# stm32f103c8t6.net
KiCad netlist of a schematic drawn in Altium Designer
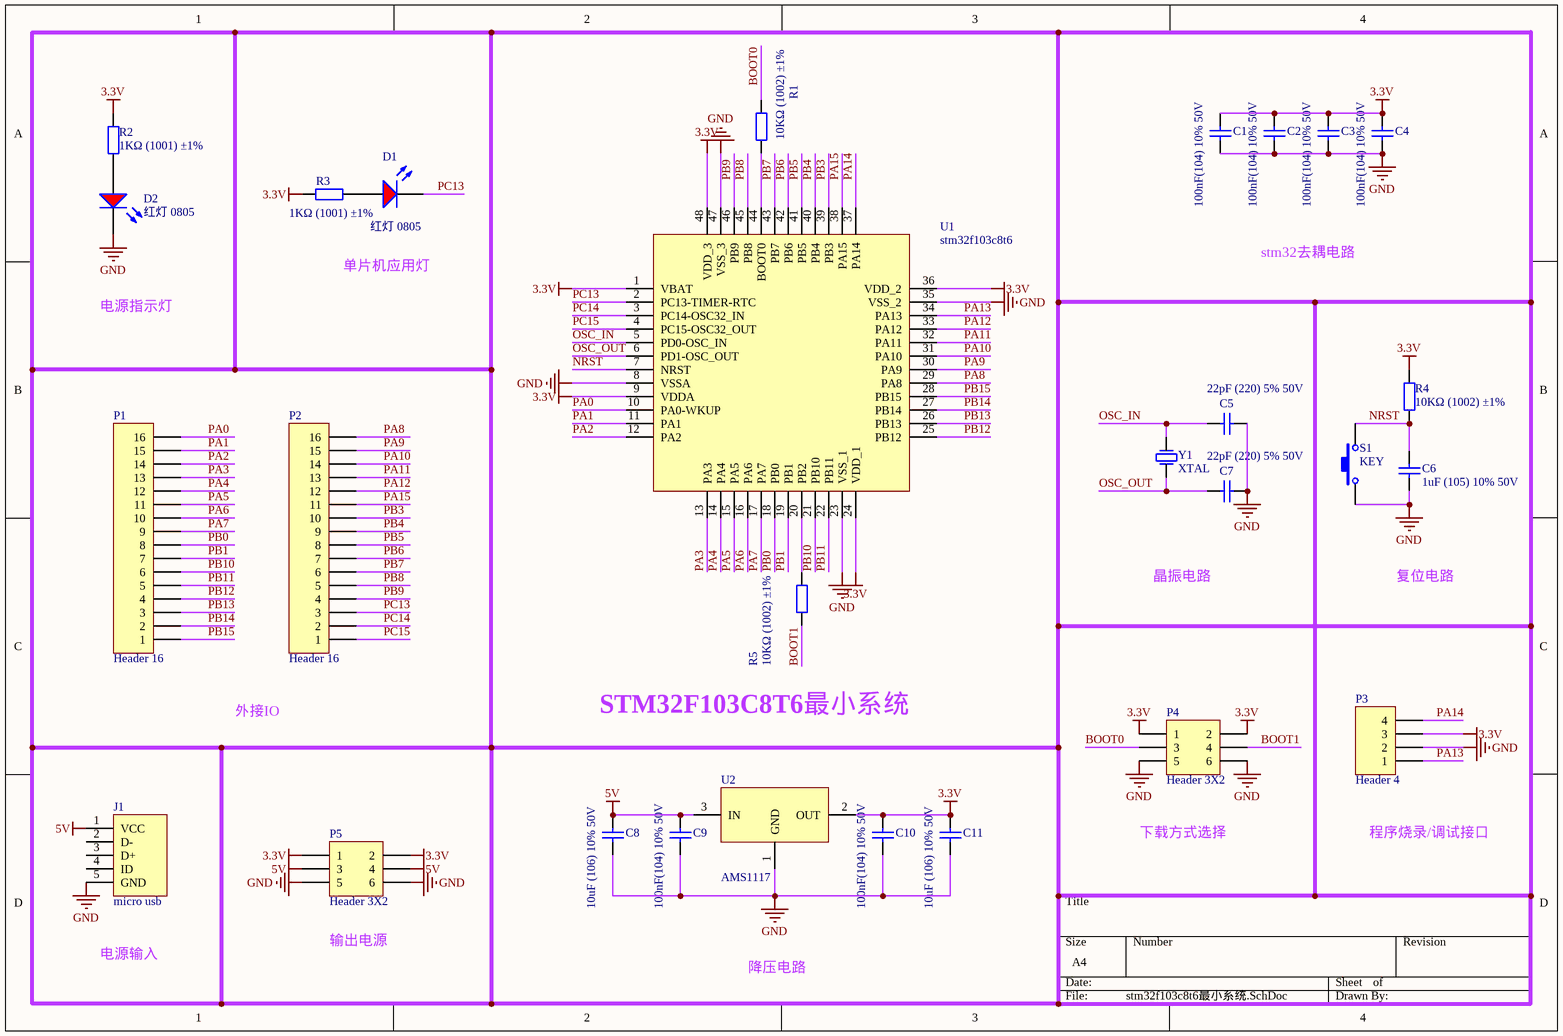
[diagram p0: stm32f103c8t6最小系统.SchDoc]

(export (version "E")
  (design (tool "Eeschema 10.0.6"))
  (components
    (comp (ref "C1")
      (value "100nF(104) 10% 50V")
      (footprint "0805_C")
      (description "贴片电容")
      (libsource (lib "Miscellaneous Devices LC") (part "0805 100nF(104) 10% 50V"))
    )
    (comp (ref "C2")
      (value "100nF(104) 10% 50V")
      (footprint "0805_C")
      (description "贴片电容")
      (libsource (lib "Miscellaneous Devices LC") (part "0805 100nF(104) 10% 50V"))
    )
    (comp (ref "C3")
      (value "100nF(104) 10% 50V")
      (footprint "0805_C")
      (description "贴片电容")
      (libsource (lib "Miscellaneous Devices LC") (part "0805 100nF(104) 10% 50V"))
    )
    (comp (ref "C4")
      (value "100nF(104) 10% 50V")
      (footprint "0805_C")
      (description "贴片电容")
      (libsource (lib "Miscellaneous Devices LC") (part "0805 100nF(104) 10% 50V"))
    )
    (comp (ref "C5")
      (value "22pF (220) 5% 50V")
      (footprint "0805_C")
      (description "贴片电容")
      (libsource (lib "Miscellaneous Devices LC") (part "0805 22pF (220) 5% 50V"))
    )
    (comp (ref "C6")
      (value "1uF (105) 10% 50V")
      (footprint "0805_C")
      (description "贴片电容")
      (libsource (lib "Miscellaneous Devices LC") (part "0805 1uF (105) 10% 50V"))
    )
    (comp (ref "C7")
      (value "22pF (220) 5% 50V")
      (footprint "0805_C")
      (description "贴片电容")
      (libsource (lib "Miscellaneous Devices LC") (part "0805 22pF (220) 5% 50V"))
    )
    (comp (ref "C8")
      (value "10uF (106) 10% 50V")
      (footprint "1206_C")
      (description "贴片电容")
      (libsource (lib "Miscellaneous Devices LC") (part "1206 10uF (106) 10% 50V"))
    )
    (comp (ref "C9")
      (value "100nF(104) 10% 50V")
      (footprint "0805_C")
      (description "贴片电容")
      (libsource (lib "Miscellaneous Devices LC") (part "0805 100nF(104) 10% 50V"))
    )
    (comp (ref "C10")
      (value "100nF(104) 10% 50V")
      (footprint "0805_C")
      (description "贴片电容")
      (libsource (lib "Miscellaneous Devices LC") (part "0805 100nF(104) 10% 50V"))
    )
    (comp (ref "C11")
      (value "10uF (106) 10% 50V")
      (footprint "1206_C")
      (description "贴片电容")
      (libsource (lib "Miscellaneous Devices LC") (part "1206 10uF (106) 10% 50V"))
    )
    (comp (ref "D1")
      (value "红灯 0805")
      (footprint "0805_LED_S1")
      (description "发光二极管")
      (libsource (lib "Miscellaneous Devices LC") (part "0805 红灯"))
    )
    (comp (ref "D2")
      (value "红灯 0805")
      (footprint "0805_LED_S1")
      (description "发光二极管")
      (libsource (lib "Miscellaneous Devices LC") (part "0805 红灯"))
    )
    (comp (ref "J1")
      (value "micro usb")
      (footprint "micro usb")
      (libsource (lib "stm32f103c8t6最小系统") (part "micro usb"))
    )
    (comp (ref "P1")
      (value "Header 16")
      (footprint "HDR1X16")
      (description "Header, 16-Pin")
      (fields (field (name "PUBLISHER") "Altium Limited"))
      (libsource (lib "base") (part "Header 16"))
    )
    (comp (ref "P2")
      (value "Header 16")
      (footprint "HDR1X16")
      (description "Header, 16-Pin")
      (fields (field (name "PUBLISHER") "Altium Limited"))
      (libsource (lib "base") (part "Header 16"))
    )
    (comp (ref "P3")
      (value "Header 4")
      (footprint "HDR1X4")
      (description "Header, 4-Pin")
      (fields (field (name "PUBLISHER") "Altium Limited"))
      (libsource (lib "base") (part "Header 4"))
    )
    (comp (ref "P4")
      (value "Header 3X2")
      (footprint "HDR2X3")
      (description "Header, 3-Pin, Dual row")
      (fields (field (name "PUBLISHER") "Altium Limited"))
      (libsource (lib "base") (part "Header 3X2"))
    )
    (comp (ref "P5")
      (value "Header 3X2")
      (footprint "HDR2X3")
      (description "Header, 3-Pin, Dual row")
      (fields (field (name "PUBLISHER") "Altium Limited"))
      (libsource (lib "base") (part "Header 3X2"))
    )
    (comp (ref "R1")
      (value "10KΩ (1002) ±1%")
      (footprint "0805_R")
      (description "贴片电阻")
      (libsource (lib "Miscellaneous Devices LC") (part "0805 10KΩ (1002) 1%"))
    )
    (comp (ref "R2")
      (value "1KΩ (1001) ±1%")
      (footprint "0805_R")
      (description "贴片电阻")
      (libsource (lib "") (part "0805 1KΩ (1001) 1%_1"))
    )
    (comp (ref "R3")
      (value "1KΩ (1001) ±1%")
      (footprint "0805_R")
      (description "贴片电阻")
      (libsource (lib "Miscellaneous Devices LC") (part "0805 1KΩ (1001) 1%"))
    )
    (comp (ref "R4")
      (value "10KΩ (1002) ±1%")
      (footprint "0805_R")
      (description "贴片电阻")
      (libsource (lib "Miscellaneous Devices LC") (part "0805 10KΩ (1002) 1%"))
    )
    (comp (ref "R5")
      (value "10KΩ (1002) ±1%")
      (footprint "0805_R")
      (description "贴片电阻")
      (libsource (lib "Miscellaneous Devices LC") (part "0805 10KΩ (1002) 1%"))
    )
    (comp (ref "S1") (value "KEY") (footprint "KEY") (libsource (lib "stm32f103c8t6最小系统") (part "KEY")))
    (comp (ref "U1")
      (value "stm32f103c8t6")
      (footprint "stm32f103c8t6")
      (libsource (lib "stm32f103c8t6最小系统") (part "stm32f103c8t6"))
    )
    (comp (ref "U2")
      (value "AMS1117")
      (footprint "AMS1117")
      (libsource (lib "stm32f103c8t6最小系统") (part "AMS1117"))
    )
    (comp (ref "Y1") (value "XTAL") (footprint "XTAL") (libsource (lib "stm32f103c8t6最小系统") (part "XTAL")))
  )
  (nets
    (net (code "1") (name "/BOOT0") (class "Default")
      (node (ref "P4") (pin "3") (pinfunction "3_3") (pintype "passive"))
      (node (ref "R1") (pin "2") (pinfunction "2_2") (pintype "passive"))
    )
    (net (code "2") (name "/BOOT1") (class "Default")
      (node (ref "P4") (pin "4") (pinfunction "4_4") (pintype "passive"))
      (node (ref "R5") (pin "1") (pinfunction "1_1") (pintype "passive"))
    )
    (net (code "3") (name "/NRST") (class "Default")
      (node (ref "C6") (pin "2") (pinfunction "2_2") (pintype "passive"))
      (node (ref "R4") (pin "1") (pinfunction "1_1") (pintype "passive"))
      (node (ref "S1") (pin "2") (pinfunction "2_2") (pintype "power_in"))
      (node (ref "U1") (pin "7") (pinfunction "NRST_7") (pintype "power_in"))
    )
    (net (code "4") (name "/OSC_IN") (class "Default")
      (node (ref "C5") (pin "1") (pinfunction "1_1") (pintype "passive"))
      (node (ref "U1") (pin "5") (pinfunction "PD0-OSC_IN_5") (pintype "power_in"))
      (node (ref "Y1") (pin "2") (pinfunction "2_2") (pintype "power_in"))
    )
    (net (code "5") (name "/OSC_OUT") (class "Default")
      (node (ref "C7") (pin "1") (pinfunction "1_1") (pintype "passive"))
      (node (ref "U1") (pin "6") (pinfunction "PD1-OSC_OUT_6") (pintype "power_in"))
      (node (ref "Y1") (pin "1") (pinfunction "1_1") (pintype "power_in"))
    )
    (net (code "6") (name "/PA0") (class "Default")
      (node (ref "P1") (pin "16") (pinfunction "16_16") (pintype "passive"))
      (node (ref "U1") (pin "10") (pinfunction "PA0-WKUP_10") (pintype "power_in"))
    )
    (net (code "7") (name "/PA1") (class "Default")
      (node (ref "P1") (pin "15") (pinfunction "15_15") (pintype "passive"))
      (node (ref "U1") (pin "11") (pinfunction "PA1_11") (pintype "power_in"))
    )
    (net (code "8") (name "/PA2") (class "Default")
      (node (ref "P1") (pin "14") (pinfunction "14_14") (pintype "passive"))
      (node (ref "U1") (pin "12") (pinfunction "PA2_12") (pintype "power_in"))
    )
    (net (code "9") (name "/PA3") (class "Default")
      (node (ref "P1") (pin "13") (pinfunction "13_13") (pintype "passive"))
      (node (ref "U1") (pin "13") (pinfunction "PA3_13") (pintype "power_in"))
    )
    (net (code "10") (name "/PA4") (class "Default")
      (node (ref "P1") (pin "12") (pinfunction "12_12") (pintype "passive"))
      (node (ref "U1") (pin "14") (pinfunction "PA4_14") (pintype "power_in"))
    )
    (net (code "11") (name "/PA5") (class "Default")
      (node (ref "P1") (pin "11") (pinfunction "11_11") (pintype "passive"))
      (node (ref "U1") (pin "15") (pinfunction "PA5_15") (pintype "power_in"))
    )
    (net (code "12") (name "/PA6") (class "Default")
      (node (ref "P1") (pin "10") (pinfunction "10_10") (pintype "passive"))
      (node (ref "U1") (pin "16") (pinfunction "PA6_16") (pintype "power_in"))
    )
    (net (code "13") (name "/PA7") (class "Default")
      (node (ref "P1") (pin "9") (pinfunction "9_9") (pintype "passive"))
      (node (ref "U1") (pin "17") (pinfunction "PA7_17") (pintype "power_in"))
    )
    (net (code "14") (name "/PA8") (class "Default")
      (node (ref "P2") (pin "16") (pinfunction "16_16") (pintype "passive"))
      (node (ref "U1") (pin "29") (pinfunction "PA8_29") (pintype "power_in"))
    )
    (net (code "15") (name "/PA9") (class "Default")
      (node (ref "P2") (pin "15") (pinfunction "15_15") (pintype "passive"))
      (node (ref "U1") (pin "30") (pinfunction "PA9_30") (pintype "power_in"))
    )
    (net (code "16") (name "/PA10") (class "Default")
      (node (ref "P2") (pin "14") (pinfunction "14_14") (pintype "passive"))
      (node (ref "U1") (pin "31") (pinfunction "PA10_31") (pintype "power_in"))
    )
    (net (code "17") (name "/PA11") (class "Default")
      (node (ref "P2") (pin "13") (pinfunction "13_13") (pintype "passive"))
      (node (ref "U1") (pin "32") (pinfunction "PA11_32") (pintype "power_in"))
    )
    (net (code "18") (name "/PA12") (class "Default")
      (node (ref "P2") (pin "12") (pinfunction "12_12") (pintype "passive"))
      (node (ref "U1") (pin "33") (pinfunction "PA12_33") (pintype "power_in"))
    )
    (net (code "19") (name "/PA13") (class "Default")
      (node (ref "P3") (pin "1") (pinfunction "1_1") (pintype "passive"))
      (node (ref "U1") (pin "34") (pinfunction "PA13_34") (pintype "power_in"))
    )
    (net (code "20") (name "/PA14") (class "Default")
      (node (ref "P3") (pin "4") (pinfunction "4_4") (pintype "passive"))
      (node (ref "U1") (pin "37") (pinfunction "PA14_37") (pintype "power_in"))
    )
    (net (code "21") (name "/PA15") (class "Default")
      (node (ref "P2") (pin "11") (pinfunction "11_11") (pintype "passive"))
      (node (ref "U1") (pin "38") (pinfunction "PA15_38") (pintype "power_in"))
    )
    (net (code "22") (name "/PB0") (class "Default")
      (node (ref "P1") (pin "8") (pinfunction "8_8") (pintype "passive"))
      (node (ref "U1") (pin "18") (pinfunction "PB0_18") (pintype "power_in"))
    )
    (net (code "23") (name "/PB1") (class "Default")
      (node (ref "P1") (pin "7") (pinfunction "7_7") (pintype "passive"))
      (node (ref "U1") (pin "19") (pinfunction "PB1_19") (pintype "power_in"))
    )
    (net (code "24") (name "/PB3") (class "Default")
      (node (ref "P2") (pin "10") (pinfunction "10_10") (pintype "passive"))
      (node (ref "U1") (pin "39") (pinfunction "PB3_39") (pintype "power_in"))
    )
    (net (code "25") (name "/PB4") (class "Default")
      (node (ref "P2") (pin "9") (pinfunction "9_9") (pintype "passive"))
      (node (ref "U1") (pin "40") (pinfunction "PB4_40") (pintype "power_in"))
    )
    (net (code "26") (name "/PB5") (class "Default")
      (node (ref "P2") (pin "8") (pinfunction "8_8") (pintype "passive"))
      (node (ref "U1") (pin "41") (pinfunction "PB5_41") (pintype "power_in"))
    )
    (net (code "27") (name "/PB6") (class "Default")
      (node (ref "P2") (pin "7") (pinfunction "7_7") (pintype "passive"))
      (node (ref "U1") (pin "42") (pinfunction "PB6_42") (pintype "power_in"))
    )
    (net (code "28") (name "/PB7") (class "Default")
      (node (ref "P2") (pin "6") (pinfunction "6_6") (pintype "passive"))
      (node (ref "U1") (pin "43") (pinfunction "PB7_43") (pintype "power_in"))
    )
    (net (code "29") (name "/PB8") (class "Default")
      (node (ref "P2") (pin "5") (pinfunction "5_5") (pintype "passive"))
      (node (ref "U1") (pin "45") (pinfunction "PB8_45") (pintype "power_in"))
    )
    (net (code "30") (name "/PB9") (class "Default")
      (node (ref "P2") (pin "4") (pinfunction "4_4") (pintype "passive"))
      (node (ref "U1") (pin "46") (pinfunction "PB9_46") (pintype "power_in"))
    )
    (net (code "31") (name "/PB10") (class "Default")
      (node (ref "P1") (pin "6") (pinfunction "6_6") (pintype "passive"))
      (node (ref "U1") (pin "21") (pinfunction "PB10_21") (pintype "power_in"))
    )
    (net (code "32") (name "/PB11") (class "Default")
      (node (ref "P1") (pin "5") (pinfunction "5_5") (pintype "passive"))
      (node (ref "U1") (pin "22") (pinfunction "PB11_22") (pintype "power_in"))
    )
    (net (code "33") (name "/PB12") (class "Default")
      (node (ref "P1") (pin "4") (pinfunction "4_4") (pintype "passive"))
      (node (ref "U1") (pin "25") (pinfunction "PB12_25") (pintype "power_in"))
    )
    (net (code "34") (name "/PB13") (class "Default")
      (node (ref "P1") (pin "3") (pinfunction "3_3") (pintype "passive"))
      (node (ref "U1") (pin "26") (pinfunction "PB13_26") (pintype "power_in"))
    )
    (net (code "35") (name "/PB14") (class "Default")
      (node (ref "P1") (pin "2") (pinfunction "2_2") (pintype "passive"))
      (node (ref "U1") (pin "27") (pinfunction "PB14_27") (pintype "power_in"))
    )
    (net (code "36") (name "/PB15") (class "Default")
      (node (ref "P1") (pin "1") (pinfunction "1_1") (pintype "passive"))
      (node (ref "U1") (pin "28") (pinfunction "PB15_28") (pintype "power_in"))
    )
    (net (code "37") (name "/PC13") (class "Default")
      (node (ref "D1") (pin "K") (pinfunction "K_K") (pintype "passive"))
      (node (ref "P2") (pin "3") (pinfunction "3_3") (pintype "passive"))
      (node (ref "U1") (pin "2") (pinfunction "PC13-TIMER-RTC_2") (pintype "power_in"))
    )
    (net (code "38") (name "/PC14") (class "Default")
      (node (ref "P2") (pin "2") (pinfunction "2_2") (pintype "passive"))
      (node (ref "U1") (pin "3") (pinfunction "PC14-OSC32_IN_3") (pintype "power_in"))
    )
    (net (code "39") (name "/PC15") (class "Default")
      (node (ref "P2") (pin "1") (pinfunction "1_1") (pintype "passive"))
      (node (ref "U1") (pin "4") (pinfunction "PC15-OSC32_OUT_4") (pintype "power_in"))
    )
    (net (code "40") (name "3.3V") (class "Default")
      (node (ref "C1") (pin "2") (pinfunction "2_2") (pintype "passive"))
      (node (ref "C10") (pin "2") (pinfunction "2_2") (pintype "passive"))
      (node (ref "C11") (pin "2") (pinfunction "2_2") (pintype "passive"))
      (node (ref "C2") (pin "2") (pinfunction "2_2") (pintype "passive"))
      (node (ref "C3") (pin "2") (pinfunction "2_2") (pintype "passive"))
      (node (ref "C4") (pin "2") (pinfunction "2_2") (pintype "passive"))
      (node (ref "P3") (pin "3") (pinfunction "3_3") (pintype "passive"))
      (node (ref "P4") (pin "1") (pinfunction "1_1") (pintype "passive"))
      (node (ref "P4") (pin "2") (pinfunction "2_2") (pintype "passive"))
      (node (ref "P5") (pin "1") (pinfunction "1_1") (pintype "passive"))
      (node (ref "P5") (pin "2") (pinfunction "2_2") (pintype "passive"))
      (node (ref "R2") (pin "2") (pinfunction "2_2") (pintype "passive"))
      (node (ref "R3") (pin "2") (pinfunction "2_2") (pintype "passive"))
      (node (ref "R4") (pin "2") (pinfunction "2_2") (pintype "passive"))
      (node (ref "U1") (pin "1") (pinfunction "VBAT_1") (pintype "power_in"))
      (node (ref "U1") (pin "24") (pinfunction "VDD_1_24") (pintype "power_in"))
      (node (ref "U1") (pin "36") (pinfunction "VDD_2_36") (pintype "power_in"))
      (node (ref "U1") (pin "48") (pinfunction "VDD_3_48") (pintype "power_in"))
      (node (ref "U1") (pin "9") (pinfunction "VDDA_9") (pintype "power_in"))
      (node (ref "U2") (pin "2") (pinfunction "OUT_2") (pintype "power_in"))
    )
    (net (code "41") (name "5V") (class "Default")
      (node (ref "C8") (pin "2") (pinfunction "2_2") (pintype "passive"))
      (node (ref "C9") (pin "2") (pinfunction "2_2") (pintype "passive"))
      (node (ref "J1") (pin "1") (pinfunction "VCC_1") (pintype "passive"))
      (node (ref "P5") (pin "3") (pinfunction "3_3") (pintype "passive"))
      (node (ref "P5") (pin "4") (pinfunction "4_4") (pintype "passive"))
      (node (ref "U2") (pin "3") (pinfunction "IN_3") (pintype "power_in"))
    )
    (net (code "42") (name "GND") (class "Default")
      (node (ref "C1") (pin "1") (pinfunction "1_1") (pintype "passive"))
      (node (ref "C10") (pin "1") (pinfunction "1_1") (pintype "passive"))
      (node (ref "C11") (pin "1") (pinfunction "1_1") (pintype "passive"))
      (node (ref "C2") (pin "1") (pinfunction "1_1") (pintype "passive"))
      (node (ref "C3") (pin "1") (pinfunction "1_1") (pintype "passive"))
      (node (ref "C4") (pin "1") (pinfunction "1_1") (pintype "passive"))
      (node (ref "C5") (pin "2") (pinfunction "2_2") (pintype "passive"))
      (node (ref "C6") (pin "1") (pinfunction "1_1") (pintype "passive"))
      (node (ref "C7") (pin "2") (pinfunction "2_2") (pintype "passive"))
      (node (ref "C8") (pin "1") (pinfunction "1_1") (pintype "passive"))
      (node (ref "C9") (pin "1") (pinfunction "1_1") (pintype "passive"))
      (node (ref "D2") (pin "K") (pinfunction "K_K") (pintype "passive"))
      (node (ref "J1") (pin "5") (pinfunction "GND_5") (pintype "passive"))
      (node (ref "P3") (pin "2") (pinfunction "2_2") (pintype "passive"))
      (node (ref "P4") (pin "5") (pinfunction "5_5") (pintype "passive"))
      (node (ref "P4") (pin "6") (pinfunction "6_6") (pintype "passive"))
      (node (ref "P5") (pin "5") (pinfunction "5_5") (pintype "passive"))
      (node (ref "P5") (pin "6") (pinfunction "6_6") (pintype "passive"))
      (node (ref "S1") (pin "1") (pinfunction "1_1") (pintype "power_in"))
      (node (ref "U1") (pin "23") (pinfunction "VSS_1_23") (pintype "power_in"))
      (node (ref "U1") (pin "35") (pinfunction "VSS_2_35") (pintype "power_in"))
      (node (ref "U1") (pin "47") (pinfunction "VSS_3_47") (pintype "power_in"))
      (node (ref "U1") (pin "8") (pinfunction "VSSA_8") (pintype "power_in"))
      (node (ref "U2") (pin "1") (pinfunction "GND_1") (pintype "power_in"))
    )
    (net (code "43") (name "Net-(D1-PadA)") (class "Default")
      (node (ref "D1") (pin "A") (pinfunction "A_A") (pintype "passive"))
      (node (ref "R3") (pin "1") (pinfunction "1_1") (pintype "passive"))
    )
    (net (code "44") (name "Net-(D2-PadA)") (class "Default")
      (node (ref "D2") (pin "A") (pinfunction "A_A") (pintype "passive"))
      (node (ref "R2") (pin "1") (pinfunction "1_1") (pintype "passive"))
    )
    (net (code "45") (name "Net-(U1-BOOT0)") (class "Default")
      (node (ref "R1") (pin "1") (pinfunction "1_1") (pintype "passive"))
      (node (ref "U1") (pin "44") (pinfunction "BOOT0_44") (pintype "power_in"))
    )
    (net (code "46") (name "Net-(U1-PB2)") (class "Default")
      (node (ref "R5") (pin "2") (pinfunction "2_2") (pintype "passive"))
      (node (ref "U1") (pin "20") (pinfunction "PB2_20") (pintype "power_in"))
    )
    (net (code "47") (name "unconnected-(J1-D+-Pad3)") (class "Default")
      (node (ref "J1") (pin "3") (pinfunction "D+_3") (pintype "passive"))
    )
    (net (code "48") (name "unconnected-(J1-D--Pad2)") (class "Default")
      (node (ref "J1") (pin "2") (pinfunction "D-_2") (pintype "passive"))
    )
    (net (code "49") (name "unconnected-(J1-ID-Pad4)") (class "Default")
      (node (ref "J1") (pin "4") (pinfunction "ID_4") (pintype "passive"))
    )
  )
)
